# ATtiny_45_85_development_board.net
KiCad netlist of a schematic drawn in EAGLE
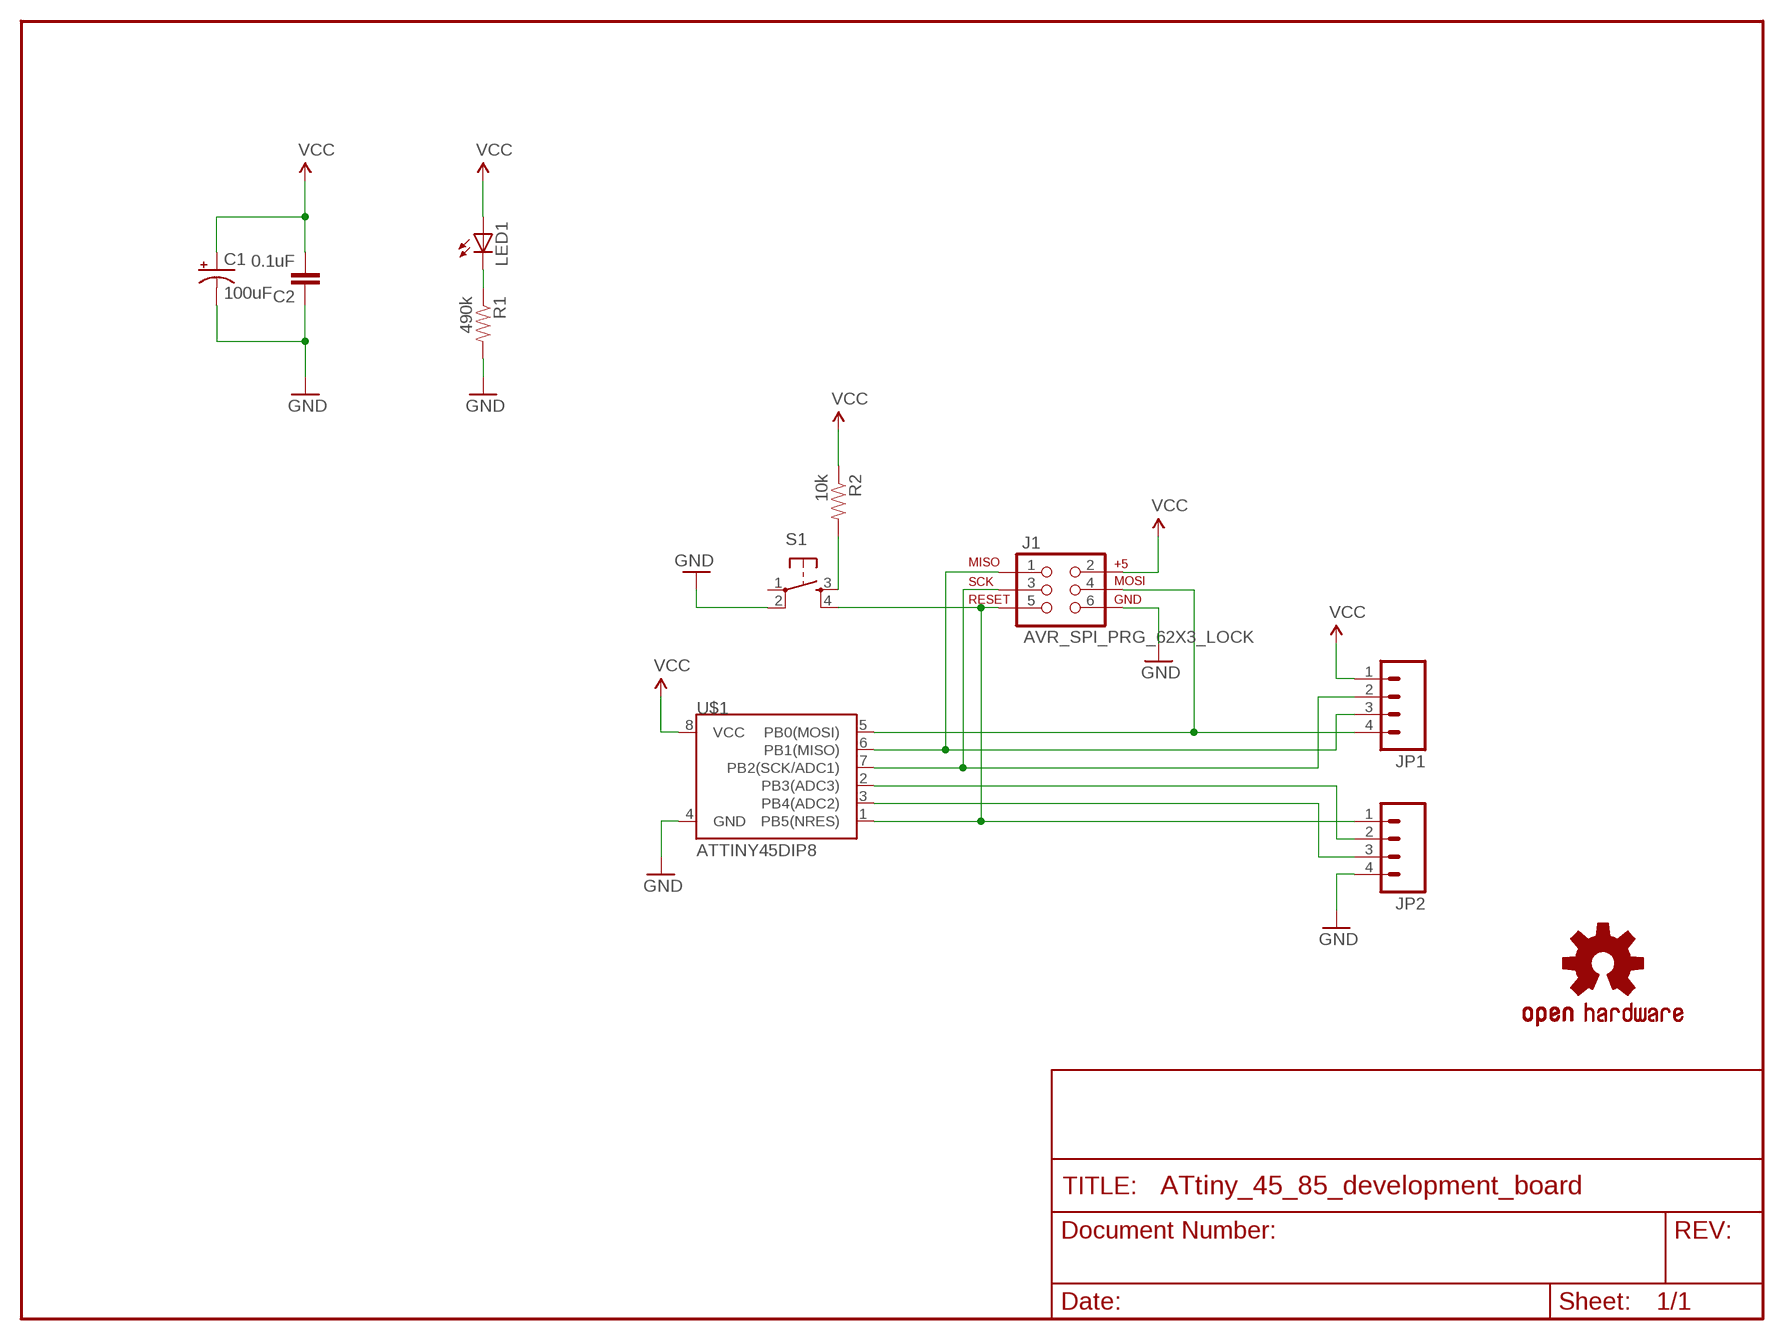
[diagram p0: schematic, sheet 1]

(export (version "E")
  (design (tool "Eeschema 10.0.6"))
  (components
    (comp (ref "C1")
      (value "100uF")
      (footprint "eagle-import:CPOL-RADIAL-100UF-25V")
      (libsource (lib "eagle-import") (part "CAP_POLPTH1"))
    )
    (comp (ref "C2")
      (value "0.1uF")
      (footprint "eagle-import:CAP-PTH-5MM")
      (libsource (lib "eagle-import") (part "CAPPTH1"))
    )
    (comp (ref "J1")
      (value "AVR_SPI_PRG_62X3_LOCK")
      (footprint "eagle-import:2X3_LOCK")
      (libsource (lib "eagle-import") (part "AVR_SPI_PRG_62X3_LOCK"))
    )
    (comp (ref "JP1")
      (value "M04LOCK")
      (footprint "eagle-import:1X04_LOCK")
      (libsource (lib "eagle-import") (part "M04LOCK"))
    )
    (comp (ref "JP2")
      (value "M04LOCK")
      (footprint "eagle-import:1X04_LOCK")
      (libsource (lib "eagle-import") (part "M04LOCK"))
    )
    (comp (ref "LED1")
      (value "LED5MM")
      (footprint "eagle-import:LED5MM")
      (libsource (lib "eagle-import") (part "LED5MM"))
    )
    (comp (ref "R1")
      (value "490k")
      (footprint "eagle-import:AXIAL-0.4")
      (libsource (lib "eagle-import") (part "RESISTORPTH-1/4W"))
    )
    (comp (ref "R2")
      (value "10k")
      (footprint "eagle-import:AXIAL-0.4")
      (libsource (lib "eagle-import") (part "RESISTORPTH-1/4W"))
    )
    (comp (ref "S1")
      (value "TAC_SWITCHPTH")
      (footprint "eagle-import:TACTILE-PTH")
      (libsource (lib "eagle-import") (part "TAC_SWITCHPTH"))
    )
    (comp (ref "U$1")
      (value "ATTINY45DIP8")
      (footprint "eagle-import:DIP08")
      (libsource (lib "eagle-import") (part "ATTINY45DIP8"))
    )
    (comp (ref "U$2")
      (value "OSHW-LOGOS")
      (footprint "eagle-import:OSHW-LOGO-S")
      (libsource (lib "eagle-import") (part "OSHW-LOGOS"))
    )
  )
  (nets
    (net (code "1") (name "GND") (class "Default")
      (node (ref "C1") (pin "2") (pinfunction "-_2") (pintype "passive"))
      (node (ref "C2") (pin "1") (pinfunction "1_1") (pintype "passive"))
      (node (ref "J1") (pin "6") (pinfunction "6_6") (pintype "passive"))
      (node (ref "JP2") (pin "4") (pinfunction "4_4") (pintype "passive"))
      (node (ref "R1") (pin "P$2") (pinfunction "2_P$2") (pintype "passive"))
      (node (ref "S1") (pin "2") (pinfunction "2_2") (pintype "passive"))
      (node (ref "U$1") (pin "4") (pinfunction "GND_4") (pintype "bidirectional"))
    )
    (net (code "2") (name "Net-(LED1-C)") (class "Default")
      (node (ref "LED1") (pin "K") (pinfunction "C_K") (pintype "passive"))
      (node (ref "R1") (pin "P$1") (pinfunction "1_P$1") (pintype "passive"))
    )
    (net (code "3") (name "Net-(R2-2)") (class "Default")
      (node (ref "R2") (pin "P$2") (pinfunction "2_P$2") (pintype "passive"))
      (node (ref "S1") (pin "3") (pinfunction "3_3") (pintype "passive"))
    )
    (net (code "4") (name "Net-(U$1-PB0(MOSI))") (class "Default")
      (node (ref "J1") (pin "4") (pinfunction "4_4") (pintype "passive"))
      (node (ref "JP1") (pin "4") (pinfunction "4_4") (pintype "passive"))
      (node (ref "U$1") (pin "5") (pinfunction "PB0(MOSI)_5") (pintype "bidirectional"))
    )
    (net (code "5") (name "Net-(U$1-PB1(MISO))") (class "Default")
      (node (ref "J1") (pin "1") (pinfunction "1_1") (pintype "passive"))
      (node (ref "JP1") (pin "3") (pinfunction "3_3") (pintype "passive"))
      (node (ref "U$1") (pin "6") (pinfunction "PB1(MISO)_6") (pintype "bidirectional"))
    )
    (net (code "6") (name "Net-(U$1-PB2(SCK{slash}ADC1))") (class "Default")
      (node (ref "J1") (pin "3") (pinfunction "3_3") (pintype "passive"))
      (node (ref "JP1") (pin "2") (pinfunction "2_2") (pintype "passive"))
      (node (ref "U$1") (pin "7") (pinfunction "PB2(SCK/ADC1)_7") (pintype "bidirectional"))
    )
    (net (code "7") (name "Net-(U$1-PB3(ADC3))") (class "Default")
      (node (ref "JP2") (pin "2") (pinfunction "2_2") (pintype "passive"))
      (node (ref "U$1") (pin "2") (pinfunction "PB3(ADC3)_2") (pintype "bidirectional"))
    )
    (net (code "8") (name "Net-(U$1-PB4(ADC2))") (class "Default")
      (node (ref "JP2") (pin "3") (pinfunction "3_3") (pintype "passive"))
      (node (ref "U$1") (pin "3") (pinfunction "PB4(ADC2)_3") (pintype "bidirectional"))
    )
    (net (code "9") (name "Net-(U$1-PB5(NRES))") (class "Default")
      (node (ref "J1") (pin "5") (pinfunction "5_5") (pintype "passive"))
      (node (ref "JP2") (pin "1") (pinfunction "1_1") (pintype "passive"))
      (node (ref "S1") (pin "4") (pinfunction "4_4") (pintype "passive"))
      (node (ref "U$1") (pin "1") (pinfunction "PB5(NRES)_1") (pintype "bidirectional"))
    )
    (net (code "10") (name "VCC") (class "Default")
      (node (ref "C1") (pin "1") (pinfunction "+_1") (pintype "passive"))
      (node (ref "C2") (pin "2") (pinfunction "2_2") (pintype "passive"))
      (node (ref "J1") (pin "2") (pinfunction "2_2") (pintype "passive"))
      (node (ref "JP1") (pin "1") (pinfunction "1_1") (pintype "passive"))
      (node (ref "LED1") (pin "A") (pinfunction "A_A") (pintype "passive"))
      (node (ref "R2") (pin "P$1") (pinfunction "1_P$1") (pintype "passive"))
      (node (ref "U$1") (pin "8") (pinfunction "VCC_8") (pintype "bidirectional"))
    )
    (net (code "11") (name "unconnected-(S1-Pad1)") (class "Default")
      (node (ref "S1") (pin "1") (pinfunction "1_1") (pintype "passive"))
    )
  )
)
